# Power.net
KiCad netlist of a schematic drawn in Altium Designer
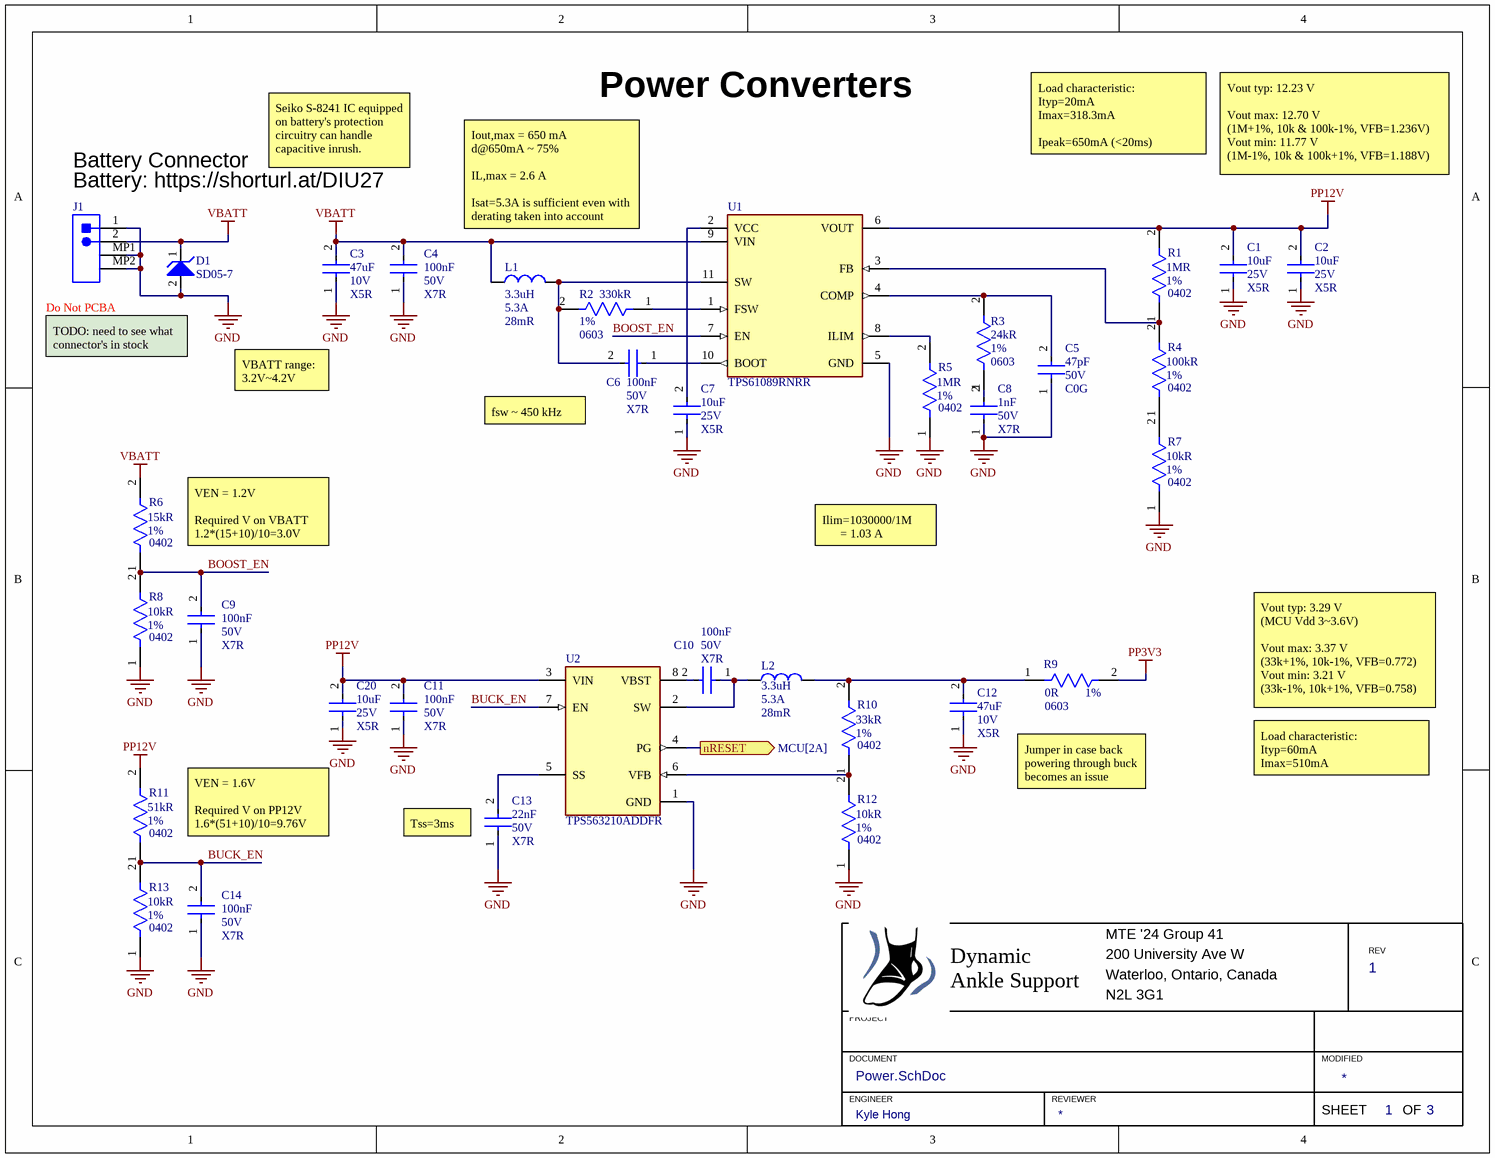
[diagram p0: Power.SchDoc]

(export (version "E")
  (design (tool "Eeschema 10.0.6"))
  (components
    (comp (ref "C1")
      (value "CL21A106KAYNNNE")
      (footprint "CAP0805")
      (description "25V 10uF X5R ±10% 0805  Multilayer Ceramic Capacitors MLCC - SMD/SMT ROHS")
      (fields
        (field (name "TOLERANCE") "10%")
        (field (name "MANUFACTURER") "Samsung Electro-Mechanics")
        (field (name "DIELECTRIC") "X5R")
        (field (name "VOLTAGE RATING") "25V")
        (field (name "CAPACITANCE") "10uF")
      )
      (libsource (lib "FYDP_library_sch") (part "CAP0805"))
    )
    (comp (ref "C2")
      (value "CL21A106KAYNNNE")
      (footprint "CAP0805")
      (description "25V 10uF X5R ±10% 0805  Multilayer Ceramic Capacitors MLCC - SMD/SMT ROHS")
      (fields
        (field (name "TOLERANCE") "10%")
        (field (name "MANUFACTURER") "Samsung Electro-Mechanics")
        (field (name "DIELECTRIC") "X5R")
        (field (name "VOLTAGE RATING") "25V")
        (field (name "CAPACITANCE") "10uF")
      )
      (libsource (lib "FYDP_library_sch") (part "CAP0805"))
    )
    (comp (ref "C3")
      (value "CL31A476MPHNNNE")
      (footprint "CAP1206")
      (description "10V 47uF X5R ±20% 1206  Multilayer Ceramic Capacitors MLCC - SMD/SMT ROHS")
      (fields
        (field (name "TOLERANCE") "20%")
        (field (name "MANUFACTURER") "Samsung Electro-Mechanics")
        (field (name "DIELECTRIC") "X5R")
        (field (name "VOLTAGE RATING") "10V")
        (field (name "CAPACITANCE") "47uF")
      )
      (libsource (lib "FYDP_library_sch") (part "CAP1206"))
    )
    (comp (ref "C4")
      (value "CL05B104KB54PNC")
      (footprint "CAP0402")
      (description "50V 100nF X7R ±10% 0402  Multilayer Ceramic Capacitors MLCC - SMD/SMT ROHS")
      (fields
        (field (name "TOLERANCE") "±20%")
        (field (name "MANUFACTURER") "Samsung Electro-Mechanics")
        (field (name "DIELECTRIC") "X7R")
        (field (name "VOLTAGE RATING") "50V")
        (field (name "CAPACITANCE") "100nF")
      )
      (libsource (lib "FYDP_library_sch") (part "CAP0402"))
    )
    (comp (ref "C5")
      (value "0402CG470J500NT")
      (footprint "CAP0402")
      (description "50V 47pF C0G ±5% 0402  Multilayer Ceramic Capacitors MLCC - SMD/SMT ROHS")
      (fields
        (field (name "TOLERANCE") "±5%")
        (field (name "MANUFACTURER") "FH (Guangdong Fenghua Advanced Tech)")
        (field (name "DIELECTRIC") "C0G")
        (field (name "VOLTAGE RATING") "50V")
        (field (name "CAPACITANCE") "47pF")
      )
      (libsource (lib "FYDP_library_sch") (part "CAP0402"))
    )
    (comp (ref "C6")
      (value "CL05B104KB54PNC")
      (footprint "CAP0402")
      (description "50V 100nF X7R ±10% 0402  Multilayer Ceramic Capacitors MLCC - SMD/SMT ROHS")
      (fields
        (field (name "TOLERANCE") "±20%")
        (field (name "MANUFACTURER") "Samsung Electro-Mechanics")
        (field (name "DIELECTRIC") "X7R")
        (field (name "VOLTAGE RATING") "50V")
        (field (name "CAPACITANCE") "100nF")
      )
      (libsource (lib "FYDP_library_sch") (part "CAP0402"))
    )
    (comp (ref "C7")
      (value "CL21A106KAYNNNE")
      (footprint "CAP0805")
      (description "25V 10uF X5R ±10% 0805  Multilayer Ceramic Capacitors MLCC - SMD/SMT ROHS")
      (fields
        (field (name "TOLERANCE") "10%")
        (field (name "MANUFACTURER") "Samsung Electro-Mechanics")
        (field (name "DIELECTRIC") "X5R")
        (field (name "VOLTAGE RATING") "25V")
        (field (name "CAPACITANCE") "10uF")
      )
      (libsource (lib "FYDP_library_sch") (part "CAP0805"))
    )
    (comp (ref "C8")
      (value "0402B102K500NT")
      (footprint "CAP0402")
      (description "50V 1nF X7R ±10% 0402  Multilayer Ceramic Capacitors MLCC - SMD/SMT ROHS")
      (fields
        (field (name "TOLERANCE") "±10%")
        (field (name "MANUFACTURER") "FH (Guangdong Fenghua Advanced Tech)")
        (field (name "DIELECTRIC") "X7R")
        (field (name "VOLTAGE RATING") "50V")
        (field (name "CAPACITANCE") "1nF")
      )
      (libsource (lib "FYDP_library_sch") (part "CAP0402"))
    )
    (comp (ref "C9")
      (value "CL05B104KB54PNC")
      (footprint "CAP0402")
      (description "50V 100nF X7R ±10% 0402  Multilayer Ceramic Capacitors MLCC - SMD/SMT ROHS")
      (fields
        (field (name "TOLERANCE") "±20%")
        (field (name "MANUFACTURER") "Samsung Electro-Mechanics")
        (field (name "DIELECTRIC") "X7R")
        (field (name "VOLTAGE RATING") "50V")
        (field (name "CAPACITANCE") "100nF")
      )
      (libsource (lib "FYDP_library_sch") (part "CAP0402"))
    )
    (comp (ref "C10")
      (value "CL05B104KB54PNC")
      (footprint "CAP0402")
      (description "50V 100nF X7R ±10% 0402  Multilayer Ceramic Capacitors MLCC - SMD/SMT ROHS")
      (fields
        (field (name "TOLERANCE") "±20%")
        (field (name "MANUFACTURER") "Samsung Electro-Mechanics")
        (field (name "DIELECTRIC") "X7R")
        (field (name "VOLTAGE RATING") "50V")
        (field (name "CAPACITANCE") "100nF")
      )
      (libsource (lib "FYDP_library_sch") (part "CAP0402"))
    )
    (comp (ref "C11")
      (value "CL05B104KB54PNC")
      (footprint "CAP0402")
      (description "50V 100nF X7R ±10% 0402  Multilayer Ceramic Capacitors MLCC - SMD/SMT ROHS")
      (fields
        (field (name "TOLERANCE") "±20%")
        (field (name "MANUFACTURER") "Samsung Electro-Mechanics")
        (field (name "DIELECTRIC") "X7R")
        (field (name "VOLTAGE RATING") "50V")
        (field (name "CAPACITANCE") "100nF")
      )
      (libsource (lib "FYDP_library_sch") (part "CAP0402"))
    )
    (comp (ref "C12")
      (value "CL31A476MPHNNNE")
      (footprint "CAP1206")
      (description "10V 47uF X5R ±20% 1206  Multilayer Ceramic Capacitors MLCC - SMD/SMT ROHS")
      (fields
        (field (name "TOLERANCE") "20%")
        (field (name "MANUFACTURER") "Samsung Electro-Mechanics")
        (field (name "DIELECTRIC") "X5R")
        (field (name "VOLTAGE RATING") "10V")
        (field (name "CAPACITANCE") "47uF")
      )
      (libsource (lib "FYDP_library_sch") (part "CAP1206"))
    )
    (comp (ref "C13")
      (value "0402B223K500NT")
      (footprint "CAP0402")
      (description "50V 22nF X7R ±10% 0402  Multilayer Ceramic Capacitors MLCC - SMD/SMT ROHS")
      (fields
        (field (name "TOLERANCE") "10%")
        (field (name "MANUFACTURER") "FH (Guangdong Fenghua Advanced Tech)")
        (field (name "DIELECTRIC") "X7R")
        (field (name "VOLTAGE RATING") "50V")
        (field (name "CAPACITANCE") "22nF")
      )
      (libsource (lib "FYDP_library_sch") (part "CAP0402"))
    )
    (comp (ref "C14")
      (value "CL05B104KB54PNC")
      (footprint "CAP0402")
      (description "50V 100nF X7R ±10% 0402  Multilayer Ceramic Capacitors MLCC - SMD/SMT ROHS")
      (fields
        (field (name "TOLERANCE") "±20%")
        (field (name "MANUFACTURER") "Samsung Electro-Mechanics")
        (field (name "DIELECTRIC") "X7R")
        (field (name "VOLTAGE RATING") "50V")
        (field (name "CAPACITANCE") "100nF")
      )
      (libsource (lib "FYDP_library_sch") (part "CAP0402"))
    )
    (comp (ref "C20")
      (value "CL21A106KAYNNNE")
      (footprint "CAP0805")
      (description "25V 10uF X5R ±10% 0805  Multilayer Ceramic Capacitors MLCC - SMD/SMT ROHS")
      (fields
        (field (name "TOLERANCE") "10%")
        (field (name "MANUFACTURER") "Samsung Electro-Mechanics")
        (field (name "DIELECTRIC") "X5R")
        (field (name "VOLTAGE RATING") "25V")
        (field (name "CAPACITANCE") "10uF")
      )
      (libsource (lib "FYDP_library_sch") (part "CAP0805"))
    )
    (comp (ref "D1")
      (value "SD05-7")
      (footprint "SD05-7")
      (description "TVS UNI14.5V 6.2V 5V SOD-323")
      (fields (field (name "MANUFACTURER") "Diodes Incorporated"))
      (libsource (lib "FYDP_library_sch") (part "SD05-7"))
    )
    (comp (ref "J1")
      (value "S2B-PH-SM4-TB(LF)(SN)")
      (footprint "JST- S2B-PH-SM4-TB(LF)(SN)-2_V")
      (description "Male Header, Pitch 2 mm, 1 x 2 Position, Height 5.5 mm, -25 to 85 degC, RoHS, Tape and Reel")
      (libsource (lib "Altium Content Vault") (part "CN-1P-2M-R2"))
    )
    (comp (ref "L1")
      (value "TMPA0503S-3R3MN-D")
      (footprint "TMPA0503S-3R3MN-D")
      (description "INDUCTOR 5.3A 3.3uH ±20% SMD Power Inductors ROHS")
      (fields
        (field (name "MANUFACTURER") "TAI-TECH")
        (field (name "TOLERANCE") "20%")
        (field (name "DC RESISTANCE") "28mR")
        (field (name "ISAT(MIN)") "5.3A")
        (field (name "INDUCTANCE") "3.3uH")
      )
      (libsource (lib "FYDP_library_sch") (part "TMPA0503S-3R3MN-D"))
    )
    (comp (ref "L2")
      (value "TMPA0503S-3R3MN-D")
      (footprint "TMPA0503S-3R3MN-D")
      (description "INDUCTOR 5.3A 3.3uH ±20% SMD Power Inductors ROHS")
      (fields
        (field (name "MANUFACTURER") "TAI-TECH")
        (field (name "TOLERANCE") "20%")
        (field (name "DC RESISTANCE") "28mR")
        (field (name "ISAT(MIN)") "5.3A")
        (field (name "INDUCTANCE") "3.3uH")
      )
      (libsource (lib "FYDP_library_sch") (part "TMPA0503S-3R3MN-D"))
    )
    (comp (ref "R1")
      (value "0402WGF1004TCE")
      (footprint "RES0402")
      (description "62.5mW Thick Film Resistors ±100ppm/℃ ±1% 1MΩ 0402  Chip Resistor - Surface Mount ROHS")
      (fields
        (field (name "MANUFACTURER") "UNI-ROYAL(Uniroyal Elec)")
        (field (name "TOLERANCE") "1%")
        (field (name "RESISTANCE") "1MR")
        (field (name "PACKAGE") "0402")
      )
      (libsource (lib "FYDP_library_sch") (part "RES0402"))
    )
    (comp (ref "R2")
      (value "0603WAF3303T5E")
      (footprint "RES0603")
      (description "100mW Thick Film Resistors ±100ppm/℃ ±1% 330kΩ 0603  Chip Resistor - Surface Mount ROHS")
      (fields
        (field (name "MANUFACTURER") "UNI-ROYAL(Uniroyal Elec)")
        (field (name "TOLERANCE") "1%")
        (field (name "RESISTANCE") "330kR")
        (field (name "PACKAGE") "0603")
      )
      (libsource (lib "FYDP_library_sch") (part "RES0603"))
    )
    (comp (ref "R3")
      (value "0603WAF2402T5E")
      (footprint "RES0603")
      (description "100mW Thick Film Resistors ±100ppm/℃ ±1% 24kΩ 0603  Chip Resistor - Surface Mount ROHS")
      (fields
        (field (name "MANUFACTURER") "UNI-ROYAL(Uniroyal Elec)")
        (field (name "TOLERANCE") "1%")
        (field (name "RESISTANCE") "24kR")
        (field (name "PACKAGE") "0603")
      )
      (libsource (lib "FYDP_library_sch") (part "RES0603"))
    )
    (comp (ref "R4")
      (value "0402WGF1003TCE")
      (footprint "RES0402")
      (description "62.5mW Thick Film Resistors ±100ppm/℃ ±1% 100kΩ 0402  Chip Resistor - Surface Mount ROHS")
      (fields
        (field (name "MANUFACTURER") "UNI-ROYAL(Uniroyal Elec)")
        (field (name "TOLERANCE") "1%")
        (field (name "RESISTANCE") "100kR")
        (field (name "PACKAGE") "0402")
      )
      (libsource (lib "FYDP_library_sch") (part "RES0402"))
    )
    (comp (ref "R5")
      (value "0402WGF1004TCE")
      (footprint "RES0402")
      (description "62.5mW Thick Film Resistors ±100ppm/℃ ±1% 1MΩ 0402  Chip Resistor - Surface Mount ROHS")
      (fields
        (field (name "MANUFACTURER") "UNI-ROYAL(Uniroyal Elec)")
        (field (name "TOLERANCE") "1%")
        (field (name "RESISTANCE") "1MR")
        (field (name "PACKAGE") "0402")
      )
      (libsource (lib "FYDP_library_sch") (part "RES0402"))
    )
    (comp (ref "R6")
      (value "0402WGF1502TCE")
      (footprint "RES0402")
      (description "62.5mW Thick Film Resistors ±100ppm/℃ ±1% 15kΩ 0402  Chip Resistor - Surface Mount ROHS")
      (fields
        (field (name "MANUFACTURER") "UNI-ROYAL(Uniroyal Elec)")
        (field (name "TOLERANCE") "1%")
        (field (name "RESISTANCE") "15kR")
        (field (name "PACKAGE") "0402")
      )
      (libsource (lib "FYDP_library_sch") (part "RES0402"))
    )
    (comp (ref "R7")
      (value "0402WGF1002TCE")
      (footprint "RES0402")
      (description "62.5mW Thick Film Resistors ±100ppm/℃ ±1% 10kΩ 0402  Chip Resistor - Surface Mount ROHS")
      (fields
        (field (name "MANUFACTURER") "UNI-ROYAL(Uniroyal Elec)")
        (field (name "TOLERANCE") "1%")
        (field (name "RESISTANCE") "10kR")
        (field (name "PACKAGE") "0402")
      )
      (libsource (lib "FYDP_library_sch") (part "RES0402"))
    )
    (comp (ref "R8")
      (value "0402WGF1002TCE")
      (footprint "RES0402")
      (description "62.5mW Thick Film Resistors ±100ppm/℃ ±1% 10kΩ 0402  Chip Resistor - Surface Mount ROHS")
      (fields
        (field (name "MANUFACTURER") "UNI-ROYAL(Uniroyal Elec)")
        (field (name "TOLERANCE") "1%")
        (field (name "RESISTANCE") "10kR")
        (field (name "PACKAGE") "0402")
      )
      (libsource (lib "FYDP_library_sch") (part "RES0402"))
    )
    (comp (ref "R9")
      (value "0603WAF0000T5E")
      (footprint "RES0603")
      (description "100mW Thick Film Resistors ±1% 0Ω 0603  Chip Resistor - Surface Mount ROHS")
      (fields
        (field (name "MANUFACTURER") "UNI-ROYAL(Uniroyal Elec)")
        (field (name "TOLERANCE") "1%")
        (field (name "RESISTANCE") "0R")
        (field (name "PACKAGE") "0603")
      )
      (libsource (lib "FYDP_library_sch") (part "RES0603"))
    )
    (comp (ref "R10")
      (value "0402WGF3302TCE")
      (footprint "RES0402")
      (description "62.5mW Thick Film Resistors ±100ppm/℃ ±1% 33kΩ 0402  Chip Resistor - Surface Mount ROHS")
      (fields
        (field (name "MANUFACTURER") "UNI-ROYAL(Uniroyal Elec)")
        (field (name "TOLERANCE") "1%")
        (field (name "RESISTANCE") "33kR")
        (field (name "PACKAGE") "0402")
      )
      (libsource (lib "FYDP_library_sch") (part "RES0402"))
    )
    (comp (ref "R11")
      (value "0402WGF5102TCE")
      (footprint "RES0402")
      (description "62.5mW Thick Film Resistors ±100ppm/℃ ±1% 51kΩ 0402  Chip Resistor - Surface Mount ROHS")
      (fields
        (field (name "MANUFACTURER") "UNI-ROYAL(Uniroyal Elec)")
        (field (name "TOLERANCE") "1%")
        (field (name "RESISTANCE") "51kR")
        (field (name "PACKAGE") "0402")
      )
      (libsource (lib "FYDP_library_sch") (part "RES0402"))
    )
    (comp (ref "R12")
      (value "0402WGF1002TCE")
      (footprint "RES0402")
      (description "62.5mW Thick Film Resistors ±100ppm/℃ ±1% 10kΩ 0402  Chip Resistor - Surface Mount ROHS")
      (fields
        (field (name "MANUFACTURER") "UNI-ROYAL(Uniroyal Elec)")
        (field (name "TOLERANCE") "1%")
        (field (name "RESISTANCE") "10kR")
        (field (name "PACKAGE") "0402")
      )
      (libsource (lib "FYDP_library_sch") (part "RES0402"))
    )
    (comp (ref "R13")
      (value "0402WGF1002TCE")
      (footprint "RES0402")
      (description "62.5mW Thick Film Resistors ±100ppm/℃ ±1% 10kΩ 0402  Chip Resistor - Surface Mount ROHS")
      (fields
        (field (name "MANUFACTURER") "UNI-ROYAL(Uniroyal Elec)")
        (field (name "TOLERANCE") "1%")
        (field (name "RESISTANCE") "10kR")
        (field (name "PACKAGE") "0402")
      )
      (libsource (lib "FYDP_library_sch") (part "RES0402"))
    )
    (comp (ref "U1")
      (value "TPS61089RNRR")
      (footprint "FP-RNR0011A-MFG")
      (description "IC REG BOOST ADJ 7A 11VQFN")
      (fields
        (field (name "MANUFACTURER") "Texas Instruments")
        (field (name "OCTOPART") "https://octopart.com/tps61089rnrr-texas+instruments-68059594")
      )
      (libsource (lib "Altium Content Vault") (part "a261192ae58a3958df181bc9456d026"))
    )
    (comp (ref "U2")
      (value "TPS563210ADDFR")
      (footprint "TPS563210ADDFR")
      (description "IC REG BUCK ADJ 3A SOT-23-8")
      (fields (field (name "MANUFACTURER") "Texas Instruments"))
      (libsource (lib "FYDP_library_sch") (part "TPS563210ADDFR"))
    )
  )
  (nets
    (net (code "1") (name "/BOOST_EN") (class "Default")
      (node (ref "C9") (pin "2") (pinfunction "2_2") (pintype "passive"))
      (node (ref "R6") (pin "1") (pinfunction "1_1") (pintype "passive"))
      (node (ref "R8") (pin "2") (pinfunction "2_2") (pintype "passive"))
      (node (ref "U1") (pin "7") (pinfunction "EN_7") (pintype "input"))
    )
    (net (code "2") (name "/BUCK_EN") (class "Default")
      (node (ref "C14") (pin "2") (pinfunction "2_2") (pintype "passive"))
      (node (ref "R11") (pin "1") (pinfunction "1_1") (pintype "passive"))
      (node (ref "R13") (pin "2") (pinfunction "2_2") (pintype "passive"))
      (node (ref "U2") (pin "7") (pinfunction "EN_7") (pintype "input"))
    )
    (net (code "3") (name "/nRESET") (class "Default")
      (node (ref "U2") (pin "4") (pinfunction "PG_4") (pintype "output"))
    )
    (net (code "4") (name "GND") (class "Default")
      (node (ref "C1") (pin "1") (pinfunction "1_1") (pintype "passive"))
      (node (ref "C11") (pin "1") (pinfunction "1_1") (pintype "passive"))
      (node (ref "C12") (pin "1") (pinfunction "1_1") (pintype "passive"))
      (node (ref "C13") (pin "1") (pinfunction "1_1") (pintype "passive"))
      (node (ref "C14") (pin "1") (pinfunction "1_1") (pintype "passive"))
      (node (ref "C2") (pin "1") (pinfunction "1_1") (pintype "passive"))
      (node (ref "C20") (pin "1") (pinfunction "1_1") (pintype "passive"))
      (node (ref "C3") (pin "1") (pinfunction "1_1") (pintype "passive"))
      (node (ref "C4") (pin "1") (pinfunction "1_1") (pintype "passive"))
      (node (ref "C5") (pin "1") (pinfunction "1_1") (pintype "passive"))
      (node (ref "C7") (pin "1") (pinfunction "1_1") (pintype "passive"))
      (node (ref "C8") (pin "1") (pinfunction "1_1") (pintype "passive"))
      (node (ref "C9") (pin "1") (pinfunction "1_1") (pintype "passive"))
      (node (ref "D1") (pin "2") (pinfunction "2_2") (pintype "passive"))
      (node (ref "J1") (pin "1") (pinfunction "1_1") (pintype "passive"))
      (node (ref "J1") (pin "MP1") (pinfunction "MP1_MP1") (pintype "passive"))
      (node (ref "J1") (pin "MP2") (pinfunction "MP2_MP2") (pintype "passive"))
      (node (ref "R12") (pin "1") (pinfunction "1_1") (pintype "passive"))
      (node (ref "R13") (pin "1") (pinfunction "1_1") (pintype "passive"))
      (node (ref "R5") (pin "1") (pinfunction "1_1") (pintype "passive"))
      (node (ref "R7") (pin "1") (pinfunction "1_1") (pintype "passive"))
      (node (ref "R8") (pin "1") (pinfunction "1_1") (pintype "passive"))
      (node (ref "U1") (pin "5") (pinfunction "GND_5") (pintype "power_in"))
      (node (ref "U2") (pin "1") (pinfunction "GND_1") (pintype "passive"))
    )
    (net (code "5") (name "Net-(C8-Pad2)") (class "Default")
      (node (ref "C8") (pin "2") (pinfunction "2_2") (pintype "passive"))
      (node (ref "R3") (pin "1") (pinfunction "1_1") (pintype "passive"))
    )
    (net (code "6") (name "Net-(C12-Pad2)") (class "Default")
      (node (ref "C12") (pin "2") (pinfunction "2_2") (pintype "passive"))
      (node (ref "L2") (pin "2") (pinfunction "2_2") (pintype "passive"))
      (node (ref "R10") (pin "2") (pinfunction "2_2") (pintype "passive"))
      (node (ref "R9") (pin "1") (pinfunction "1_1") (pintype "passive"))
    )
    (net (code "7") (name "Net-(R4-Pad1)") (class "Default")
      (node (ref "R4") (pin "1") (pinfunction "1_1") (pintype "passive"))
      (node (ref "R7") (pin "2") (pinfunction "2_2") (pintype "passive"))
    )
    (net (code "8") (name "Net-(U1-BOOT)") (class "Default")
      (node (ref "C6") (pin "1") (pinfunction "1_1") (pintype "passive"))
      (node (ref "U1") (pin "10") (pinfunction "BOOT_10") (pintype "output"))
    )
    (net (code "9") (name "Net-(U1-COMP)") (class "Default")
      (node (ref "C5") (pin "2") (pinfunction "2_2") (pintype "passive"))
      (node (ref "R3") (pin "2") (pinfunction "2_2") (pintype "passive"))
      (node (ref "U1") (pin "4") (pinfunction "COMP_4") (pintype "output"))
    )
    (net (code "10") (name "Net-(U1-FB)") (class "Default")
      (node (ref "R1") (pin "1") (pinfunction "1_1") (pintype "passive"))
      (node (ref "R4") (pin "2") (pinfunction "2_2") (pintype "passive"))
      (node (ref "U1") (pin "3") (pinfunction "FB_3") (pintype "input"))
    )
    (net (code "11") (name "Net-(U1-FSW)") (class "Default")
      (node (ref "R2") (pin "1") (pinfunction "1_1") (pintype "passive"))
      (node (ref "U1") (pin "1") (pinfunction "FSW_1") (pintype "input"))
    )
    (net (code "12") (name "Net-(U1-ILIM)") (class "Default")
      (node (ref "R5") (pin "2") (pinfunction "2_2") (pintype "passive"))
      (node (ref "U1") (pin "8") (pinfunction "ILIM_8") (pintype "output"))
    )
    (net (code "13") (name "Net-(U1-SW)") (class "Default")
      (node (ref "C6") (pin "2") (pinfunction "2_2") (pintype "passive"))
      (node (ref "L1") (pin "2") (pinfunction "2_2") (pintype "passive"))
      (node (ref "R2") (pin "2") (pinfunction "2_2") (pintype "passive"))
      (node (ref "U1") (pin "11") (pinfunction "SW_11") (pintype "power_in"))
    )
    (net (code "14") (name "Net-(U1-VCC)") (class "Default")
      (node (ref "C7") (pin "2") (pinfunction "2_2") (pintype "passive"))
      (node (ref "U1") (pin "2") (pinfunction "VCC_2") (pintype "power_in"))
    )
    (net (code "15") (name "Net-(U2-SS)") (class "Default")
      (node (ref "C13") (pin "2") (pinfunction "2_2") (pintype "passive"))
      (node (ref "U2") (pin "5") (pinfunction "SS_5") (pintype "passive"))
    )
    (net (code "16") (name "Net-(U2-SW)") (class "Default")
      (node (ref "C10") (pin "1") (pinfunction "1_1") (pintype "passive"))
      (node (ref "L2") (pin "1") (pinfunction "1_1") (pintype "passive"))
      (node (ref "U2") (pin "2") (pinfunction "SW_2") (pintype "passive"))
    )
    (net (code "17") (name "Net-(U2-VBST)") (class "Default")
      (node (ref "C10") (pin "2") (pinfunction "2_2") (pintype "passive"))
      (node (ref "U2") (pin "8") (pinfunction "VBST_8") (pintype "passive"))
    )
    (net (code "18") (name "Net-(U2-VFB)") (class "Default")
      (node (ref "R10") (pin "1") (pinfunction "1_1") (pintype "passive"))
      (node (ref "R12") (pin "2") (pinfunction "2_2") (pintype "passive"))
      (node (ref "U2") (pin "6") (pinfunction "VFB_6") (pintype "input"))
    )
    (net (code "19") (name "PP3V3") (class "Default")
      (node (ref "R9") (pin "2") (pinfunction "2_2") (pintype "passive"))
    )
    (net (code "20") (name "PP12V") (class "Default")
      (node (ref "C1") (pin "2") (pinfunction "2_2") (pintype "passive"))
      (node (ref "C11") (pin "2") (pinfunction "2_2") (pintype "passive"))
      (node (ref "C2") (pin "2") (pinfunction "2_2") (pintype "passive"))
      (node (ref "C20") (pin "2") (pinfunction "2_2") (pintype "passive"))
      (node (ref "R1") (pin "2") (pinfunction "2_2") (pintype "passive"))
      (node (ref "R11") (pin "2") (pinfunction "2_2") (pintype "passive"))
      (node (ref "U1") (pin "6") (pinfunction "VOUT_6") (pintype "power_in"))
      (node (ref "U2") (pin "3") (pinfunction "VIN_3") (pintype "passive"))
    )
    (net (code "21") (name "VBATT") (class "Default")
      (node (ref "C3") (pin "2") (pinfunction "2_2") (pintype "passive"))
      (node (ref "C4") (pin "2") (pinfunction "2_2") (pintype "passive"))
      (node (ref "D1") (pin "1") (pinfunction "1_1") (pintype "passive"))
      (node (ref "J1") (pin "2") (pinfunction "2_2") (pintype "passive"))
      (node (ref "L1") (pin "1") (pinfunction "1_1") (pintype "passive"))
      (node (ref "R6") (pin "2") (pinfunction "2_2") (pintype "passive"))
      (node (ref "U1") (pin "9") (pinfunction "VIN_9") (pintype "power_in"))
    )
  )
)
